# hv507_connector.net
KiCad netlist of a schematic drawn in EAGLE
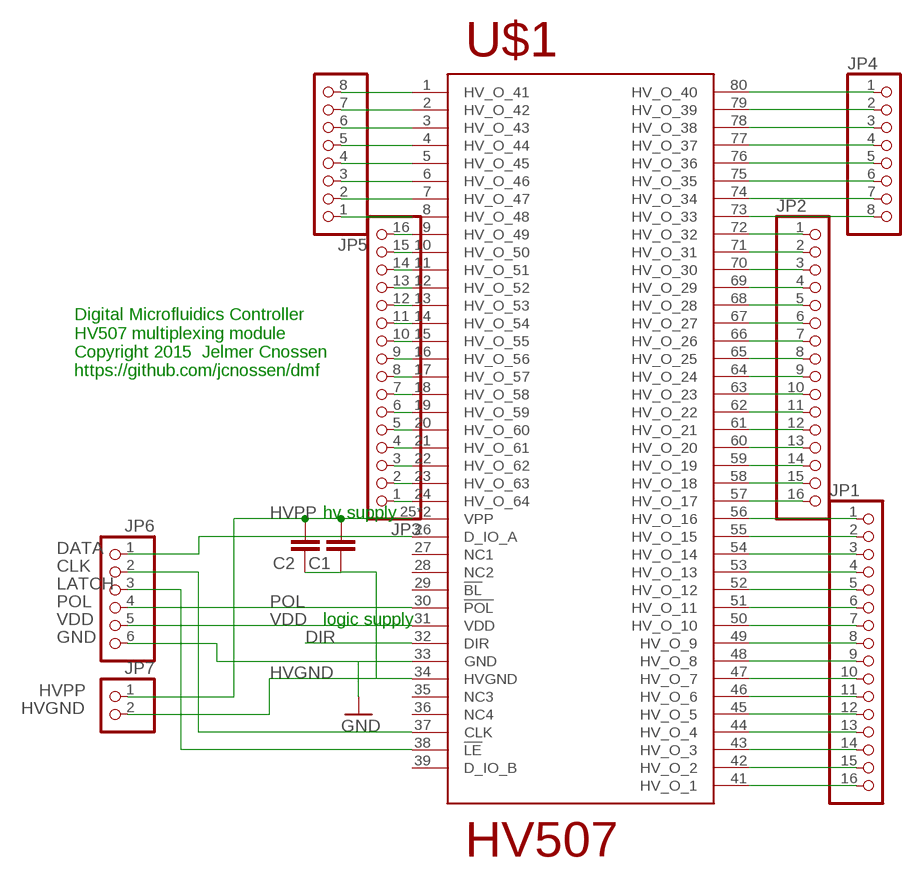
[diagram p0: schematic, sheet 1]

(export (version "E")
  (design (tool "Eeschema 10.0.6"))
  (components
    (comp (ref "C1")
      (value "C-EUC1812")
      (footprint "eagle-import:C1812")
      (libsource (lib "eagle-import") (part "C-EUC1812"))
    )
    (comp (ref "C2")
      (value "C-EUC1206")
      (footprint "eagle-import:C1206")
      (libsource (lib "eagle-import") (part "C-EUC1206"))
    )
    (comp (ref "JP1")
      (value "PINHD-1X16_2.54-S")
      (footprint "eagle-import:1X16-S")
      (libsource (lib "eagle-import") (part "PINHD-1X16_2.54-S"))
    )
    (comp (ref "JP2")
      (value "PINHD-1X16_2.54-S")
      (footprint "eagle-import:1X16-S")
      (libsource (lib "eagle-import") (part "PINHD-1X16_2.54-S"))
    )
    (comp (ref "JP3")
      (value "PINHD-1X16_2.54-S")
      (footprint "eagle-import:1X16-S")
      (libsource (lib "eagle-import") (part "PINHD-1X16_2.54-S"))
    )
    (comp (ref "JP4")
      (value "PINHD-1X08_2.54-S")
      (footprint "eagle-import:1X08-S")
      (libsource (lib "eagle-import") (part "PINHD-1X08_2.54-S"))
    )
    (comp (ref "JP5")
      (value "PINHD-1X08_2.54-S")
      (footprint "eagle-import:1X08-S")
      (libsource (lib "eagle-import") (part "PINHD-1X08_2.54-S"))
    )
    (comp (ref "JP6")
      (value "PINHD-1X06_2.54-S")
      (footprint "eagle-import:1X06-S")
      (libsource (lib "eagle-import") (part "PINHD-1X06_2.54-S"))
    )
    (comp (ref "JP7")
      (value "PINHD-1X02_2.54-S")
      (footprint "eagle-import:1X02-S")
      (libsource (lib "eagle-import") (part "PINHD-1X02_2.54-S"))
    )
    (comp (ref "U$1")
      (value "HV507")
      (footprint "eagle-import:HV507PG-G")
      (libsource (lib "eagle-import") (part "HV507"))
    )
  )
  (nets
    (net (code "1") (name "/CLK") (class "Default")
      (node (ref "JP6") (pin "2") (pinfunction "2_2") (pintype "passive"))
      (node (ref "U$1") (pin "37") (pinfunction "CLK_37") (pintype "bidirectional"))
    )
    (net (code "2") (name "/DATA") (class "Default")
      (node (ref "JP6") (pin "1") (pinfunction "1_1") (pintype "passive"))
      (node (ref "U$1") (pin "26") (pinfunction "D_IO_A_26") (pintype "bidirectional"))
    )
    (net (code "3") (name "/DIR") (class "Default")
      (node (ref "U$1") (pin "32") (pinfunction "DIR_32") (pintype "bidirectional"))
    )
    (net (code "4") (name "/HVGND") (class "Default")
      (node (ref "C1") (pin "1") (pinfunction "1_1") (pintype "passive"))
      (node (ref "C2") (pin "1") (pinfunction "1_1") (pintype "passive"))
      (node (ref "JP7") (pin "2") (pinfunction "2_2") (pintype "passive"))
      (node (ref "U$1") (pin "34") (pinfunction "HVGND_34") (pintype "bidirectional"))
    )
    (net (code "5") (name "/HVPP") (class "Default")
      (node (ref "C1") (pin "2") (pinfunction "2_2") (pintype "passive"))
      (node (ref "C2") (pin "2") (pinfunction "2_2") (pintype "passive"))
      (node (ref "JP7") (pin "1") (pinfunction "1_1") (pintype "passive"))
      (node (ref "U$1") (pin "25") (pinfunction "VPP_25") (pintype "bidirectional"))
      (node (ref "U$1") (pin "40") (pinfunction "VPP_40") (pintype "bidirectional"))
    )
    (net (code "6") (name "/LATCH") (class "Default")
      (node (ref "JP6") (pin "3") (pinfunction "3_3") (pintype "passive"))
      (node (ref "U$1") (pin "38") (pinfunction "~{LE}_38") (pintype "bidirectional"))
    )
    (net (code "7") (name "/POL") (class "Default")
      (node (ref "JP6") (pin "4") (pinfunction "4_4") (pintype "passive"))
      (node (ref "U$1") (pin "30") (pinfunction "~{POL}_30") (pintype "bidirectional"))
    )
    (net (code "8") (name "/VDD") (class "Default")
      (node (ref "JP6") (pin "5") (pinfunction "5_5") (pintype "passive"))
      (node (ref "U$1") (pin "31") (pinfunction "VDD_31") (pintype "bidirectional"))
    )
    (net (code "9") (name "GND") (class "Default")
      (node (ref "JP6") (pin "6") (pinfunction "6_6") (pintype "passive"))
      (node (ref "U$1") (pin "33") (pinfunction "GND_33") (pintype "bidirectional"))
    )
    (net (code "10") (name "Net-(U$1-HV_O_1)") (class "Default")
      (node (ref "JP1") (pin "16") (pinfunction "16_16") (pintype "passive"))
      (node (ref "U$1") (pin "41") (pinfunction "HV_O_1_41") (pintype "bidirectional"))
    )
    (net (code "11") (name "Net-(U$1-HV_O_2)") (class "Default")
      (node (ref "JP1") (pin "15") (pinfunction "15_15") (pintype "passive"))
      (node (ref "U$1") (pin "42") (pinfunction "HV_O_2_42") (pintype "bidirectional"))
    )
    (net (code "12") (name "Net-(U$1-HV_O_3)") (class "Default")
      (node (ref "JP1") (pin "14") (pinfunction "14_14") (pintype "passive"))
      (node (ref "U$1") (pin "43") (pinfunction "HV_O_3_43") (pintype "bidirectional"))
    )
    (net (code "13") (name "Net-(U$1-HV_O_4)") (class "Default")
      (node (ref "JP1") (pin "13") (pinfunction "13_13") (pintype "passive"))
      (node (ref "U$1") (pin "44") (pinfunction "HV_O_4_44") (pintype "bidirectional"))
    )
    (net (code "14") (name "Net-(U$1-HV_O_5)") (class "Default")
      (node (ref "JP1") (pin "12") (pinfunction "12_12") (pintype "passive"))
      (node (ref "U$1") (pin "45") (pinfunction "HV_O_5_45") (pintype "bidirectional"))
    )
    (net (code "15") (name "Net-(U$1-HV_O_6)") (class "Default")
      (node (ref "JP1") (pin "11") (pinfunction "11_11") (pintype "passive"))
      (node (ref "U$1") (pin "46") (pinfunction "HV_O_6_46") (pintype "bidirectional"))
    )
    (net (code "16") (name "Net-(U$1-HV_O_7)") (class "Default")
      (node (ref "JP1") (pin "10") (pinfunction "10_10") (pintype "passive"))
      (node (ref "U$1") (pin "47") (pinfunction "HV_O_7_47") (pintype "bidirectional"))
    )
    (net (code "17") (name "Net-(U$1-HV_O_8)") (class "Default")
      (node (ref "JP1") (pin "9") (pinfunction "9_9") (pintype "passive"))
      (node (ref "U$1") (pin "48") (pinfunction "HV_O_8_48") (pintype "bidirectional"))
    )
    (net (code "18") (name "Net-(U$1-HV_O_9)") (class "Default")
      (node (ref "JP1") (pin "8") (pinfunction "8_8") (pintype "passive"))
      (node (ref "U$1") (pin "49") (pinfunction "HV_O_9_49") (pintype "bidirectional"))
    )
    (net (code "19") (name "Net-(U$1-HV_O_10)") (class "Default")
      (node (ref "JP1") (pin "7") (pinfunction "7_7") (pintype "passive"))
      (node (ref "U$1") (pin "50") (pinfunction "HV_O_10_50") (pintype "bidirectional"))
    )
    (net (code "20") (name "Net-(U$1-HV_O_11)") (class "Default")
      (node (ref "JP1") (pin "6") (pinfunction "6_6") (pintype "passive"))
      (node (ref "U$1") (pin "51") (pinfunction "HV_O_11_51") (pintype "bidirectional"))
    )
    (net (code "21") (name "Net-(U$1-HV_O_12)") (class "Default")
      (node (ref "JP1") (pin "5") (pinfunction "5_5") (pintype "passive"))
      (node (ref "U$1") (pin "52") (pinfunction "HV_O_12_52") (pintype "bidirectional"))
    )
    (net (code "22") (name "Net-(U$1-HV_O_13)") (class "Default")
      (node (ref "JP1") (pin "4") (pinfunction "4_4") (pintype "passive"))
      (node (ref "U$1") (pin "53") (pinfunction "HV_O_13_53") (pintype "bidirectional"))
    )
    (net (code "23") (name "Net-(U$1-HV_O_14)") (class "Default")
      (node (ref "JP1") (pin "3") (pinfunction "3_3") (pintype "passive"))
      (node (ref "U$1") (pin "54") (pinfunction "HV_O_14_54") (pintype "bidirectional"))
    )
    (net (code "24") (name "Net-(U$1-HV_O_15)") (class "Default")
      (node (ref "JP1") (pin "2") (pinfunction "2_2") (pintype "passive"))
      (node (ref "U$1") (pin "55") (pinfunction "HV_O_15_55") (pintype "bidirectional"))
    )
    (net (code "25") (name "Net-(U$1-HV_O_16)") (class "Default")
      (node (ref "JP1") (pin "1") (pinfunction "1_1") (pintype "passive"))
      (node (ref "U$1") (pin "56") (pinfunction "HV_O_16_56") (pintype "bidirectional"))
    )
    (net (code "26") (name "Net-(U$1-HV_O_17)") (class "Default")
      (node (ref "JP2") (pin "16") (pinfunction "16_16") (pintype "passive"))
      (node (ref "U$1") (pin "57") (pinfunction "HV_O_17_57") (pintype "bidirectional"))
    )
    (net (code "27") (name "Net-(U$1-HV_O_18)") (class "Default")
      (node (ref "JP2") (pin "15") (pinfunction "15_15") (pintype "passive"))
      (node (ref "U$1") (pin "58") (pinfunction "HV_O_18_58") (pintype "bidirectional"))
    )
    (net (code "28") (name "Net-(U$1-HV_O_19)") (class "Default")
      (node (ref "JP2") (pin "14") (pinfunction "14_14") (pintype "passive"))
      (node (ref "U$1") (pin "59") (pinfunction "HV_O_19_59") (pintype "bidirectional"))
    )
    (net (code "29") (name "Net-(U$1-HV_O_20)") (class "Default")
      (node (ref "JP2") (pin "13") (pinfunction "13_13") (pintype "passive"))
      (node (ref "U$1") (pin "60") (pinfunction "HV_O_20_60") (pintype "bidirectional"))
    )
    (net (code "30") (name "Net-(U$1-HV_O_21)") (class "Default")
      (node (ref "JP2") (pin "12") (pinfunction "12_12") (pintype "passive"))
      (node (ref "U$1") (pin "61") (pinfunction "HV_O_21_61") (pintype "bidirectional"))
    )
    (net (code "31") (name "Net-(U$1-HV_O_22)") (class "Default")
      (node (ref "JP2") (pin "11") (pinfunction "11_11") (pintype "passive"))
      (node (ref "U$1") (pin "62") (pinfunction "HV_O_22_62") (pintype "bidirectional"))
    )
    (net (code "32") (name "Net-(U$1-HV_O_23)") (class "Default")
      (node (ref "JP2") (pin "10") (pinfunction "10_10") (pintype "passive"))
      (node (ref "U$1") (pin "63") (pinfunction "HV_O_23_63") (pintype "bidirectional"))
    )
    (net (code "33") (name "Net-(U$1-HV_O_24)") (class "Default")
      (node (ref "JP2") (pin "9") (pinfunction "9_9") (pintype "passive"))
      (node (ref "U$1") (pin "64") (pinfunction "HV_O_24_64") (pintype "bidirectional"))
    )
    (net (code "34") (name "Net-(U$1-HV_O_25)") (class "Default")
      (node (ref "JP2") (pin "8") (pinfunction "8_8") (pintype "passive"))
      (node (ref "U$1") (pin "65") (pinfunction "HV_O_25_65") (pintype "bidirectional"))
    )
    (net (code "35") (name "Net-(U$1-HV_O_26)") (class "Default")
      (node (ref "JP2") (pin "7") (pinfunction "7_7") (pintype "passive"))
      (node (ref "U$1") (pin "66") (pinfunction "HV_O_26_66") (pintype "bidirectional"))
    )
    (net (code "36") (name "Net-(U$1-HV_O_27)") (class "Default")
      (node (ref "JP2") (pin "6") (pinfunction "6_6") (pintype "passive"))
      (node (ref "U$1") (pin "67") (pinfunction "HV_O_27_67") (pintype "bidirectional"))
    )
    (net (code "37") (name "Net-(U$1-HV_O_28)") (class "Default")
      (node (ref "JP2") (pin "5") (pinfunction "5_5") (pintype "passive"))
      (node (ref "U$1") (pin "68") (pinfunction "HV_O_28_68") (pintype "bidirectional"))
    )
    (net (code "38") (name "Net-(U$1-HV_O_29)") (class "Default")
      (node (ref "JP2") (pin "4") (pinfunction "4_4") (pintype "passive"))
      (node (ref "U$1") (pin "69") (pinfunction "HV_O_29_69") (pintype "bidirectional"))
    )
    (net (code "39") (name "Net-(U$1-HV_O_30)") (class "Default")
      (node (ref "JP2") (pin "3") (pinfunction "3_3") (pintype "passive"))
      (node (ref "U$1") (pin "70") (pinfunction "HV_O_30_70") (pintype "bidirectional"))
    )
    (net (code "40") (name "Net-(U$1-HV_O_31)") (class "Default")
      (node (ref "JP2") (pin "2") (pinfunction "2_2") (pintype "passive"))
      (node (ref "U$1") (pin "71") (pinfunction "HV_O_31_71") (pintype "bidirectional"))
    )
    (net (code "41") (name "Net-(U$1-HV_O_32)") (class "Default")
      (node (ref "JP2") (pin "1") (pinfunction "1_1") (pintype "passive"))
      (node (ref "U$1") (pin "72") (pinfunction "HV_O_32_72") (pintype "bidirectional"))
    )
    (net (code "42") (name "Net-(U$1-HV_O_33)") (class "Default")
      (node (ref "JP4") (pin "8") (pinfunction "8_8") (pintype "passive"))
      (node (ref "U$1") (pin "73") (pinfunction "HV_O_33_73") (pintype "bidirectional"))
    )
    (net (code "43") (name "Net-(U$1-HV_O_34)") (class "Default")
      (node (ref "JP4") (pin "7") (pinfunction "7_7") (pintype "passive"))
      (node (ref "U$1") (pin "74") (pinfunction "HV_O_34_74") (pintype "bidirectional"))
    )
    (net (code "44") (name "Net-(U$1-HV_O_35)") (class "Default")
      (node (ref "JP4") (pin "6") (pinfunction "6_6") (pintype "passive"))
      (node (ref "U$1") (pin "75") (pinfunction "HV_O_35_75") (pintype "bidirectional"))
    )
    (net (code "45") (name "Net-(U$1-HV_O_36)") (class "Default")
      (node (ref "JP4") (pin "5") (pinfunction "5_5") (pintype "passive"))
      (node (ref "U$1") (pin "76") (pinfunction "HV_O_36_76") (pintype "bidirectional"))
    )
    (net (code "46") (name "Net-(U$1-HV_O_37)") (class "Default")
      (node (ref "JP4") (pin "4") (pinfunction "4_4") (pintype "passive"))
      (node (ref "U$1") (pin "77") (pinfunction "HV_O_37_77") (pintype "bidirectional"))
    )
    (net (code "47") (name "Net-(U$1-HV_O_38)") (class "Default")
      (node (ref "JP4") (pin "3") (pinfunction "3_3") (pintype "passive"))
      (node (ref "U$1") (pin "78") (pinfunction "HV_O_38_78") (pintype "bidirectional"))
    )
    (net (code "48") (name "Net-(U$1-HV_O_39)") (class "Default")
      (node (ref "JP4") (pin "2") (pinfunction "2_2") (pintype "passive"))
      (node (ref "U$1") (pin "79") (pinfunction "HV_O_39_79") (pintype "bidirectional"))
    )
    (net (code "49") (name "Net-(U$1-HV_O_40)") (class "Default")
      (node (ref "JP4") (pin "1") (pinfunction "1_1") (pintype "passive"))
      (node (ref "U$1") (pin "80") (pinfunction "HV_O_40_80") (pintype "bidirectional"))
    )
    (net (code "50") (name "Net-(U$1-HV_O_41)") (class "Default")
      (node (ref "JP5") (pin "8") (pinfunction "8_8") (pintype "passive"))
      (node (ref "U$1") (pin "1") (pinfunction "HV_O_41_1") (pintype "bidirectional"))
    )
    (net (code "51") (name "Net-(U$1-HV_O_42)") (class "Default")
      (node (ref "JP5") (pin "7") (pinfunction "7_7") (pintype "passive"))
      (node (ref "U$1") (pin "2") (pinfunction "HV_O_42_2") (pintype "bidirectional"))
    )
    (net (code "52") (name "Net-(U$1-HV_O_43)") (class "Default")
      (node (ref "JP5") (pin "6") (pinfunction "6_6") (pintype "passive"))
      (node (ref "U$1") (pin "3") (pinfunction "HV_O_43_3") (pintype "bidirectional"))
    )
    (net (code "53") (name "Net-(U$1-HV_O_44)") (class "Default")
      (node (ref "JP5") (pin "5") (pinfunction "5_5") (pintype "passive"))
      (node (ref "U$1") (pin "4") (pinfunction "HV_O_44_4") (pintype "bidirectional"))
    )
    (net (code "54") (name "Net-(U$1-HV_O_45)") (class "Default")
      (node (ref "JP5") (pin "4") (pinfunction "4_4") (pintype "passive"))
      (node (ref "U$1") (pin "5") (pinfunction "HV_O_45_5") (pintype "bidirectional"))
    )
    (net (code "55") (name "Net-(U$1-HV_O_46)") (class "Default")
      (node (ref "JP5") (pin "3") (pinfunction "3_3") (pintype "passive"))
      (node (ref "U$1") (pin "6") (pinfunction "HV_O_46_6") (pintype "bidirectional"))
    )
    (net (code "56") (name "Net-(U$1-HV_O_47)") (class "Default")
      (node (ref "JP5") (pin "2") (pinfunction "2_2") (pintype "passive"))
      (node (ref "U$1") (pin "7") (pinfunction "HV_O_47_7") (pintype "bidirectional"))
    )
    (net (code "57") (name "Net-(U$1-HV_O_48)") (class "Default")
      (node (ref "JP5") (pin "1") (pinfunction "1_1") (pintype "passive"))
      (node (ref "U$1") (pin "8") (pinfunction "HV_O_48_8") (pintype "bidirectional"))
    )
    (net (code "58") (name "Net-(U$1-HV_O_49)") (class "Default")
      (node (ref "JP3") (pin "16") (pinfunction "16_16") (pintype "passive"))
      (node (ref "U$1") (pin "9") (pinfunction "HV_O_49_9") (pintype "bidirectional"))
    )
    (net (code "59") (name "Net-(U$1-HV_O_50)") (class "Default")
      (node (ref "JP3") (pin "15") (pinfunction "15_15") (pintype "passive"))
      (node (ref "U$1") (pin "10") (pinfunction "HV_O_50_10") (pintype "bidirectional"))
    )
    (net (code "60") (name "Net-(U$1-HV_O_51)") (class "Default")
      (node (ref "JP3") (pin "14") (pinfunction "14_14") (pintype "passive"))
      (node (ref "U$1") (pin "11") (pinfunction "HV_O_51_11") (pintype "bidirectional"))
    )
    (net (code "61") (name "Net-(U$1-HV_O_52)") (class "Default")
      (node (ref "JP3") (pin "13") (pinfunction "13_13") (pintype "passive"))
      (node (ref "U$1") (pin "12") (pinfunction "HV_O_52_12") (pintype "bidirectional"))
    )
    (net (code "62") (name "Net-(U$1-HV_O_53)") (class "Default")
      (node (ref "JP3") (pin "12") (pinfunction "12_12") (pintype "passive"))
      (node (ref "U$1") (pin "13") (pinfunction "HV_O_53_13") (pintype "bidirectional"))
    )
    (net (code "63") (name "Net-(U$1-HV_O_54)") (class "Default")
      (node (ref "JP3") (pin "11") (pinfunction "11_11") (pintype "passive"))
      (node (ref "U$1") (pin "14") (pinfunction "HV_O_54_14") (pintype "bidirectional"))
    )
    (net (code "64") (name "Net-(U$1-HV_O_55)") (class "Default")
      (node (ref "JP3") (pin "10") (pinfunction "10_10") (pintype "passive"))
      (node (ref "U$1") (pin "15") (pinfunction "HV_O_55_15") (pintype "bidirectional"))
    )
    (net (code "65") (name "Net-(U$1-HV_O_56)") (class "Default")
      (node (ref "JP3") (pin "9") (pinfunction "9_9") (pintype "passive"))
      (node (ref "U$1") (pin "16") (pinfunction "HV_O_56_16") (pintype "bidirectional"))
    )
    (net (code "66") (name "Net-(U$1-HV_O_57)") (class "Default")
      (node (ref "JP3") (pin "8") (pinfunction "8_8") (pintype "passive"))
      (node (ref "U$1") (pin "17") (pinfunction "HV_O_57_17") (pintype "bidirectional"))
    )
    (net (code "67") (name "Net-(U$1-HV_O_58)") (class "Default")
      (node (ref "JP3") (pin "7") (pinfunction "7_7") (pintype "passive"))
      (node (ref "U$1") (pin "18") (pinfunction "HV_O_58_18") (pintype "bidirectional"))
    )
    (net (code "68") (name "Net-(U$1-HV_O_59)") (class "Default")
      (node (ref "JP3") (pin "6") (pinfunction "6_6") (pintype "passive"))
      (node (ref "U$1") (pin "19") (pinfunction "HV_O_59_19") (pintype "bidirectional"))
    )
    (net (code "69") (name "Net-(U$1-HV_O_60)") (class "Default")
      (node (ref "JP3") (pin "5") (pinfunction "5_5") (pintype "passive"))
      (node (ref "U$1") (pin "20") (pinfunction "HV_O_60_20") (pintype "bidirectional"))
    )
    (net (code "70") (name "Net-(U$1-HV_O_61)") (class "Default")
      (node (ref "JP3") (pin "4") (pinfunction "4_4") (pintype "passive"))
      (node (ref "U$1") (pin "21") (pinfunction "HV_O_61_21") (pintype "bidirectional"))
    )
    (net (code "71") (name "Net-(U$1-HV_O_62)") (class "Default")
      (node (ref "JP3") (pin "3") (pinfunction "3_3") (pintype "passive"))
      (node (ref "U$1") (pin "22") (pinfunction "HV_O_62_22") (pintype "bidirectional"))
    )
    (net (code "72") (name "Net-(U$1-HV_O_63)") (class "Default")
      (node (ref "JP3") (pin "2") (pinfunction "2_2") (pintype "passive"))
      (node (ref "U$1") (pin "23") (pinfunction "HV_O_63_23") (pintype "bidirectional"))
    )
    (net (code "73") (name "Net-(U$1-HV_O_64)") (class "Default")
      (node (ref "JP3") (pin "1") (pinfunction "1_1") (pintype "passive"))
      (node (ref "U$1") (pin "24") (pinfunction "HV_O_64_24") (pintype "bidirectional"))
    )
    (net (code "74") (name "unconnected-(U$1-D_IO_B-Pad39)") (class "Default")
      (node (ref "U$1") (pin "39") (pinfunction "D_IO_B_39") (pintype "bidirectional"))
    )
    (net (code "75") (name "unconnected-(U$1-NC1-Pad27)") (class "Default")
      (node (ref "U$1") (pin "27") (pinfunction "NC1_27") (pintype "bidirectional"))
    )
    (net (code "76") (name "unconnected-(U$1-NC2-Pad28)") (class "Default")
      (node (ref "U$1") (pin "28") (pinfunction "NC2_28") (pintype "bidirectional"))
    )
    (net (code "77") (name "unconnected-(U$1-NC3-Pad35)") (class "Default")
      (node (ref "U$1") (pin "35") (pinfunction "NC3_35") (pintype "bidirectional"))
    )
    (net (code "78") (name "unconnected-(U$1-NC4-Pad36)") (class "Default")
      (node (ref "U$1") (pin "36") (pinfunction "NC4_36") (pintype "bidirectional"))
    )
    (net (code "79") (name "unconnected-(U$1-~{BL}-Pad29)") (class "Default")
      (node (ref "U$1") (pin "29") (pinfunction "~{BL}_29") (pintype "bidirectional"))
    )
  )
)
